# PinConnector_1_2.net
KiCad netlist of a schematic drawn in Altium Designer
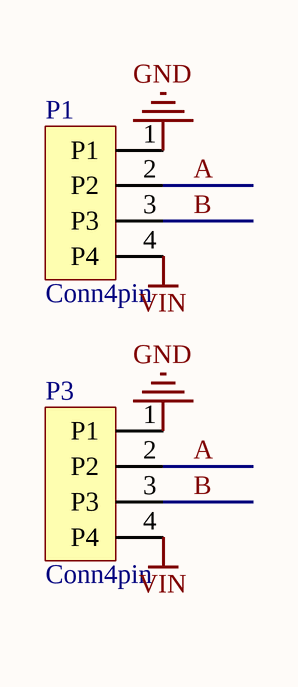
[diagram p0: PinConnector 1.2.SchDoc]

(export (version "E")
  (design (tool "Eeschema 10.0.6"))
  (components
    (comp (ref "P1")
      (value "Conn4pin")
      (footprint "Bourns 70AB/Female (4 conn)")
      (libsource (lib "SenaCorpLibSCH") (part "Conn4pin"))
    )
    (comp (ref "P3")
      (value "Conn4pin")
      (footprint "Connector 4pin 75mil space")
      (libsource (lib "SenaCorpLibSCH") (part "Conn4pin"))
    )
  )
  (nets
    (net (code "1") (name "/A") (class "Default")
      (node (ref "P1") (pin "2") (pinfunction "P2_2") (pintype "passive"))
      (node (ref "P3") (pin "2") (pinfunction "P2_2") (pintype "passive"))
    )
    (net (code "2") (name "/B") (class "Default")
      (node (ref "P1") (pin "3") (pinfunction "P3_3") (pintype "passive"))
      (node (ref "P3") (pin "3") (pinfunction "P3_3") (pintype "passive"))
    )
    (net (code "3") (name "GND") (class "Default")
      (node (ref "P1") (pin "1") (pinfunction "P1_1") (pintype "passive"))
      (node (ref "P3") (pin "1") (pinfunction "P1_1") (pintype "passive"))
    )
    (net (code "4") (name "VIN") (class "Default")
      (node (ref "P1") (pin "4") (pinfunction "P4_4") (pintype "passive"))
      (node (ref "P3") (pin "4") (pinfunction "P4_4") (pintype "passive"))
    )
  )
)
